# sonar_hotfix_3.net
KiCad netlist of a schematic drawn in EAGLE
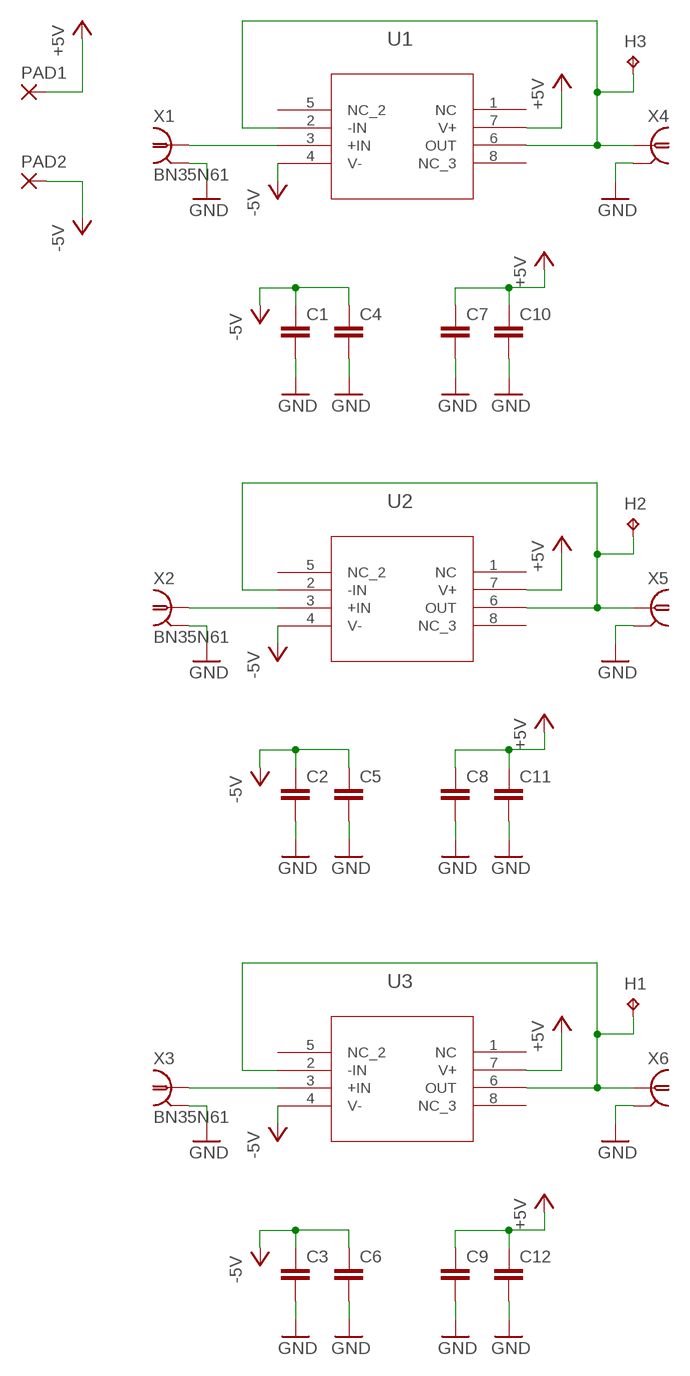
[diagram p0: schematic, sheet 1]

(export (version "E")
  (design (tool "Eeschema 10.0.6"))
  (components
    (comp (ref "C1")
      (value "C-EUC0603")
      (footprint "eagle-import:C0603")
      (libsource (lib "eagle-import") (part "C-EUC0603"))
    )
    (comp (ref "C2")
      (value "C-EUC0603")
      (footprint "eagle-import:C0603")
      (libsource (lib "eagle-import") (part "C-EUC0603"))
    )
    (comp (ref "C3")
      (value "C-EUC0603")
      (footprint "eagle-import:C0603")
      (libsource (lib "eagle-import") (part "C-EUC0603"))
    )
    (comp (ref "C4")
      (value "C-EUC0603")
      (footprint "eagle-import:C0603")
      (libsource (lib "eagle-import") (part "C-EUC0603"))
    )
    (comp (ref "C5")
      (value "C-EUC0603")
      (footprint "eagle-import:C0603")
      (libsource (lib "eagle-import") (part "C-EUC0603"))
    )
    (comp (ref "C6")
      (value "C-EUC0603")
      (footprint "eagle-import:C0603")
      (libsource (lib "eagle-import") (part "C-EUC0603"))
    )
    (comp (ref "C7")
      (value "C-EUC0603")
      (footprint "eagle-import:C0603")
      (libsource (lib "eagle-import") (part "C-EUC0603"))
    )
    (comp (ref "C8")
      (value "C-EUC0603")
      (footprint "eagle-import:C0603")
      (libsource (lib "eagle-import") (part "C-EUC0603"))
    )
    (comp (ref "C9")
      (value "C-EUC0603")
      (footprint "eagle-import:C0603")
      (libsource (lib "eagle-import") (part "C-EUC0603"))
    )
    (comp (ref "C10")
      (value "C-EUC0603")
      (footprint "eagle-import:C0603")
      (libsource (lib "eagle-import") (part "C-EUC0603"))
    )
    (comp (ref "C11")
      (value "C-EUC0603")
      (footprint "eagle-import:C0603")
      (libsource (lib "eagle-import") (part "C-EUC0603"))
    )
    (comp (ref "C12")
      (value "C-EUC0603")
      (footprint "eagle-import:C0603")
      (libsource (lib "eagle-import") (part "C-EUC0603"))
    )
    (comp (ref "H1")
      (value "TPB2,54")
      (footprint "eagle-import:B2,54")
      (libsource (lib "eagle-import") (part "TPB2,54"))
    )
    (comp (ref "H2")
      (value "TPB2,54")
      (footprint "eagle-import:B2,54")
      (libsource (lib "eagle-import") (part "TPB2,54"))
    )
    (comp (ref "H3")
      (value "TPB2,54")
      (footprint "eagle-import:B2,54")
      (libsource (lib "eagle-import") (part "TPB2,54"))
    )
    (comp (ref "PAD1")
      (value "WIREPADSMD5-2,5")
      (footprint "eagle-import:5-2,5")
      (libsource (lib "eagle-import") (part "WIREPADSMD5-2,5"))
    )
    (comp (ref "PAD2")
      (value "WIREPADSMD5-2,5")
      (footprint "eagle-import:5-2,5")
      (libsource (lib "eagle-import") (part "WIREPADSMD5-2,5"))
    )
    (comp (ref "U1")
      (value "LTC6240SO-8")
      (footprint "eagle-import:SO-8")
      (libsource (lib "eagle-import") (part "LTC6240SO-8"))
    )
    (comp (ref "U2")
      (value "LTC6240SO-8")
      (footprint "eagle-import:SO-8")
      (libsource (lib "eagle-import") (part "LTC6240SO-8"))
    )
    (comp (ref "U3")
      (value "LTC6240SO-8")
      (footprint "eagle-import:SO-8")
      (libsource (lib "eagle-import") (part "LTC6240SO-8"))
    )
    (comp (ref "X1")
      (value "BN35N61")
      (footprint "eagle-import:B35N61")
      (libsource (lib "eagle-import") (part "BN35N61"))
    )
    (comp (ref "X2")
      (value "BN35N61")
      (footprint "eagle-import:B35N61")
      (libsource (lib "eagle-import") (part "BN35N61"))
    )
    (comp (ref "X3")
      (value "BN35N61")
      (footprint "eagle-import:B35N61")
      (libsource (lib "eagle-import") (part "BN35N61"))
    )
    (comp (ref "X4")
      (value "BN35N61-HALF")
      (footprint "eagle-import:B35N61-HALF")
      (libsource (lib "eagle-import") (part "BN35N61-HALF"))
    )
    (comp (ref "X5")
      (value "BN35N61-HALF")
      (footprint "eagle-import:B35N61-HALF")
      (libsource (lib "eagle-import") (part "BN35N61-HALF"))
    )
    (comp (ref "X6")
      (value "BN35N61-HALF")
      (footprint "eagle-import:B35N61-HALF")
      (libsource (lib "eagle-import") (part "BN35N61-HALF"))
    )
  )
  (nets
    (net (code "1") (name "+5V") (class "Default")
      (node (ref "C10") (pin "1") (pinfunction "1_1") (pintype "passive"))
      (node (ref "C11") (pin "1") (pinfunction "1_1") (pintype "passive"))
      (node (ref "C12") (pin "1") (pinfunction "1_1") (pintype "passive"))
      (node (ref "C7") (pin "1") (pinfunction "1_1") (pintype "passive"))
      (node (ref "C8") (pin "1") (pinfunction "1_1") (pintype "passive"))
      (node (ref "C9") (pin "1") (pinfunction "1_1") (pintype "passive"))
      (node (ref "PAD1") (pin "1") (pinfunction "P_1") (pintype "passive"))
      (node (ref "U1") (pin "7") (pinfunction "V+_7") (pintype "power_in"))
      (node (ref "U2") (pin "7") (pinfunction "V+_7") (pintype "power_in"))
      (node (ref "U3") (pin "7") (pinfunction "V+_7") (pintype "power_in"))
    )
    (net (code "2") (name "-5V") (class "Default")
      (node (ref "C1") (pin "1") (pinfunction "1_1") (pintype "passive"))
      (node (ref "C2") (pin "1") (pinfunction "1_1") (pintype "passive"))
      (node (ref "C3") (pin "1") (pinfunction "1_1") (pintype "passive"))
      (node (ref "C4") (pin "1") (pinfunction "1_1") (pintype "passive"))
      (node (ref "C5") (pin "1") (pinfunction "1_1") (pintype "passive"))
      (node (ref "C6") (pin "1") (pinfunction "1_1") (pintype "passive"))
      (node (ref "PAD2") (pin "1") (pinfunction "P_1") (pintype "passive"))
      (node (ref "U1") (pin "4") (pinfunction "V-_4") (pintype "power_in"))
      (node (ref "U2") (pin "4") (pinfunction "V-_4") (pintype "power_in"))
      (node (ref "U3") (pin "4") (pinfunction "V-_4") (pintype "power_in"))
    )
    (net (code "3") (name "GND") (class "Default")
      (node (ref "C1") (pin "2") (pinfunction "2_2") (pintype "passive"))
      (node (ref "C10") (pin "2") (pinfunction "2_2") (pintype "passive"))
      (node (ref "C11") (pin "2") (pinfunction "2_2") (pintype "passive"))
      (node (ref "C12") (pin "2") (pinfunction "2_2") (pintype "passive"))
      (node (ref "C2") (pin "2") (pinfunction "2_2") (pintype "passive"))
      (node (ref "C3") (pin "2") (pinfunction "2_2") (pintype "passive"))
      (node (ref "C4") (pin "2") (pinfunction "2_2") (pintype "passive"))
      (node (ref "C5") (pin "2") (pinfunction "2_2") (pintype "passive"))
      (node (ref "C6") (pin "2") (pinfunction "2_2") (pintype "passive"))
      (node (ref "C7") (pin "2") (pinfunction "2_2") (pintype "passive"))
      (node (ref "C8") (pin "2") (pinfunction "2_2") (pintype "passive"))
      (node (ref "C9") (pin "2") (pinfunction "2_2") (pintype "passive"))
      (node (ref "X1") (pin "2") (pinfunction "2_2") (pintype "passive"))
      (node (ref "X1") (pin "3") (pinfunction "2_3") (pintype "passive"))
      (node (ref "X1") (pin "4") (pinfunction "2_4") (pintype "passive"))
      (node (ref "X1") (pin "5") (pinfunction "2_5") (pintype "passive"))
      (node (ref "X2") (pin "2") (pinfunction "2_2") (pintype "passive"))
      (node (ref "X2") (pin "3") (pinfunction "2_3") (pintype "passive"))
      (node (ref "X2") (pin "4") (pinfunction "2_4") (pintype "passive"))
      (node (ref "X2") (pin "5") (pinfunction "2_5") (pintype "passive"))
      (node (ref "X3") (pin "2") (pinfunction "2_2") (pintype "passive"))
      (node (ref "X3") (pin "3") (pinfunction "2_3") (pintype "passive"))
      (node (ref "X3") (pin "4") (pinfunction "2_4") (pintype "passive"))
      (node (ref "X3") (pin "5") (pinfunction "2_5") (pintype "passive"))
      (node (ref "X4") (pin "2") (pinfunction "2_2") (pintype "passive"))
      (node (ref "X4") (pin "3") (pinfunction "2_3") (pintype "passive"))
      (node (ref "X5") (pin "2") (pinfunction "2_2") (pintype "passive"))
      (node (ref "X5") (pin "3") (pinfunction "2_3") (pintype "passive"))
      (node (ref "X6") (pin "2") (pinfunction "2_2") (pintype "passive"))
      (node (ref "X6") (pin "3") (pinfunction "2_3") (pintype "passive"))
    )
    (net (code "4") (name "Net-(U1-+IN)") (class "Default")
      (node (ref "U1") (pin "3") (pinfunction "+IN_3") (pintype "input"))
      (node (ref "X1") (pin "1") (pinfunction "1_1") (pintype "passive"))
    )
    (net (code "5") (name "Net-(U1--IN)") (class "Default")
      (node (ref "H3") (pin "TP") (pinfunction "TP_TP") (pintype "input"))
      (node (ref "U1") (pin "2") (pinfunction "-IN_2") (pintype "input"))
      (node (ref "U1") (pin "6") (pinfunction "OUT_6") (pintype "output"))
      (node (ref "X4") (pin "1") (pinfunction "1_1") (pintype "passive"))
    )
    (net (code "6") (name "Net-(U2-+IN)") (class "Default")
      (node (ref "U2") (pin "3") (pinfunction "+IN_3") (pintype "input"))
      (node (ref "X2") (pin "1") (pinfunction "1_1") (pintype "passive"))
    )
    (net (code "7") (name "Net-(U2--IN)") (class "Default")
      (node (ref "H2") (pin "TP") (pinfunction "TP_TP") (pintype "input"))
      (node (ref "U2") (pin "2") (pinfunction "-IN_2") (pintype "input"))
      (node (ref "U2") (pin "6") (pinfunction "OUT_6") (pintype "output"))
      (node (ref "X5") (pin "1") (pinfunction "1_1") (pintype "passive"))
    )
    (net (code "8") (name "Net-(U3-+IN)") (class "Default")
      (node (ref "U3") (pin "3") (pinfunction "+IN_3") (pintype "input"))
      (node (ref "X3") (pin "1") (pinfunction "1_1") (pintype "passive"))
    )
    (net (code "9") (name "Net-(U3--IN)") (class "Default")
      (node (ref "H1") (pin "TP") (pinfunction "TP_TP") (pintype "input"))
      (node (ref "U3") (pin "2") (pinfunction "-IN_2") (pintype "input"))
      (node (ref "U3") (pin "6") (pinfunction "OUT_6") (pintype "output"))
      (node (ref "X6") (pin "1") (pinfunction "1_1") (pintype "passive"))
    )
    (net (code "10") (name "unconnected-(U1-NC-Pad1)") (class "Default")
      (node (ref "U1") (pin "1") (pinfunction "NC_1") (pintype "no_connect"))
    )
    (net (code "11") (name "unconnected-(U1-NC_2-Pad5)") (class "Default")
      (node (ref "U1") (pin "5") (pinfunction "NC_2_5") (pintype "no_connect"))
    )
    (net (code "12") (name "unconnected-(U1-NC_3-Pad8)") (class "Default")
      (node (ref "U1") (pin "8") (pinfunction "NC_3_8") (pintype "no_connect"))
    )
    (net (code "13") (name "unconnected-(U2-NC-Pad1)") (class "Default")
      (node (ref "U2") (pin "1") (pinfunction "NC_1") (pintype "no_connect"))
    )
    (net (code "14") (name "unconnected-(U2-NC_2-Pad5)") (class "Default")
      (node (ref "U2") (pin "5") (pinfunction "NC_2_5") (pintype "no_connect"))
    )
    (net (code "15") (name "unconnected-(U2-NC_3-Pad8)") (class "Default")
      (node (ref "U2") (pin "8") (pinfunction "NC_3_8") (pintype "no_connect"))
    )
    (net (code "16") (name "unconnected-(U3-NC-Pad1)") (class "Default")
      (node (ref "U3") (pin "1") (pinfunction "NC_1") (pintype "no_connect"))
    )
    (net (code "17") (name "unconnected-(U3-NC_2-Pad5)") (class "Default")
      (node (ref "U3") (pin "5") (pinfunction "NC_2_5") (pintype "no_connect"))
    )
    (net (code "18") (name "unconnected-(U3-NC_3-Pad8)") (class "Default")
      (node (ref "U3") (pin "8") (pinfunction "NC_3_8") (pintype "no_connect"))
    )
  )
)
